# GD32E230C8T6.net
KiCad netlist of a schematic drawn in Altium Designer
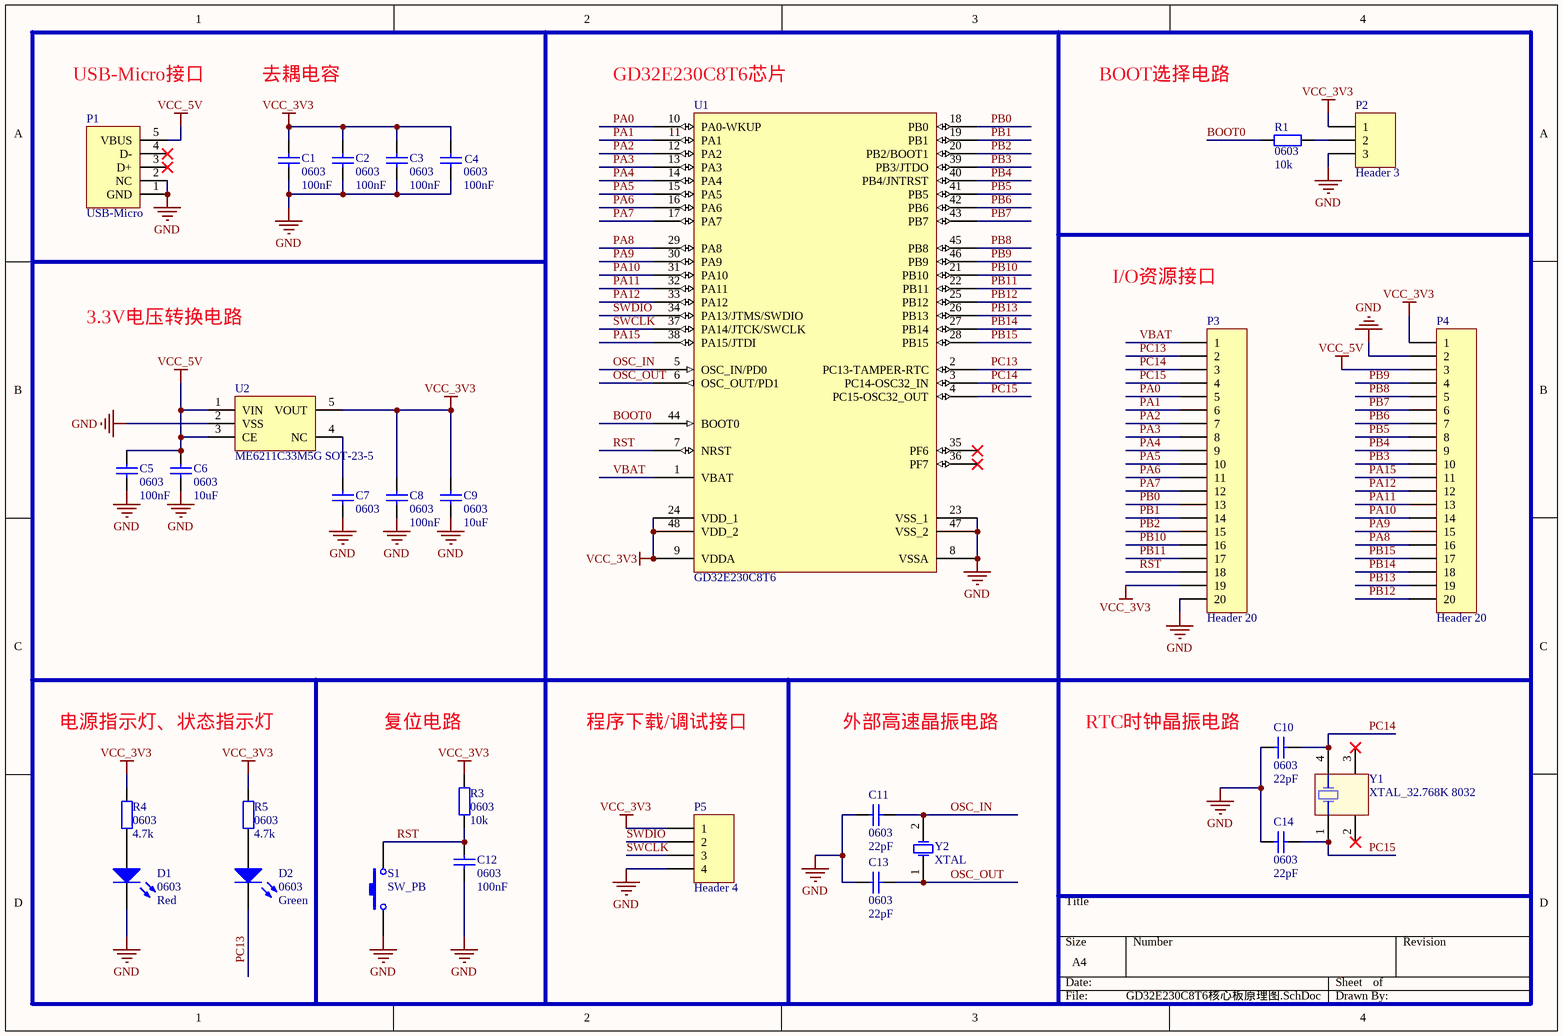
[diagram p0: GD32E230C8T6核心板原理图.SchDoc]

(export (version "E")
  (design (tool "Eeschema 10.0.6"))
  (components
    (comp (ref "C1")
      (value "100nF")
      (footprint "0603")
      (description "Capacitor 0603")
      (fields (field (name "Comment") "Cap 0603"))
      (libsource (lib "Schlib1") (part "Cap 0603"))
    )
    (comp (ref "C2")
      (value "100nF")
      (footprint "0603")
      (description "Capacitor 0603")
      (fields (field (name "Comment") "Cap 0603"))
      (libsource (lib "Schlib1") (part "Cap 0603"))
    )
    (comp (ref "C3")
      (value "100nF")
      (footprint "0603")
      (description "Capacitor 0603")
      (fields (field (name "Comment") "Cap 0603"))
      (libsource (lib "Schlib1") (part "Cap 0603"))
    )
    (comp (ref "C4")
      (value "100nF")
      (footprint "0603")
      (description "Capacitor 0603")
      (fields (field (name "Comment") "Cap 0603"))
      (libsource (lib "Schlib1") (part "Cap 0603"))
    )
    (comp (ref "C5")
      (value "100nF")
      (footprint "0603")
      (description "Capacitor 0603")
      (fields (field (name "Comment") "Cap 0603"))
      (libsource (lib "Schlib1") (part "Cap 0603"))
    )
    (comp (ref "C6")
      (value "10uF")
      (footprint "0603")
      (description "Capacitor 0603")
      (fields (field (name "Comment") "Cap 0603"))
      (libsource (lib "Schlib1") (part "Cap 0603"))
    )
    (comp (ref "C7")
      (value "Cap 0603")
      (footprint "0603")
      (description "Capacitor 0603")
      (libsource (lib "Schlib1") (part "Cap 0603"))
    )
    (comp (ref "C8")
      (value "100nF")
      (footprint "0603")
      (description "Capacitor 0603")
      (fields (field (name "Comment") "Cap 0603"))
      (libsource (lib "Schlib1") (part "Cap 0603"))
    )
    (comp (ref "C9")
      (value "10uF")
      (footprint "0603")
      (description "Capacitor 0603")
      (fields (field (name "Comment") "Cap 0603"))
      (libsource (lib "Schlib1") (part "Cap 0603"))
    )
    (comp (ref "C10")
      (value "22pF")
      (footprint "0603")
      (description "Capacitor 0603")
      (fields (field (name "Comment") "Cap 0603"))
      (libsource (lib "Schlib1") (part "Cap 0603"))
    )
    (comp (ref "C11")
      (value "22pF")
      (footprint "0603")
      (description "Capacitor 0603")
      (fields (field (name "Comment") "Cap 0603"))
      (libsource (lib "Schlib1") (part "Cap 0603"))
    )
    (comp (ref "C12")
      (value "100nF")
      (footprint "0603")
      (description "Capacitor 0603")
      (fields (field (name "Comment") "Cap 0603"))
      (libsource (lib "Schlib1") (part "Cap 0603"))
    )
    (comp (ref "C13")
      (value "22pF")
      (footprint "0603")
      (description "Capacitor 0603")
      (fields (field (name "Comment") "Cap 0603"))
      (libsource (lib "Schlib1") (part "Cap 0603"))
    )
    (comp (ref "C14")
      (value "22pF")
      (footprint "0603")
      (description "Capacitor 0603")
      (fields (field (name "Comment") "Cap 0603"))
      (libsource (lib "Schlib1") (part "Cap 0603"))
    )
    (comp (ref "D1")
      (value "Red")
      (footprint "0603")
      (description "LED 0603")
      (libsource (lib "Schlib1") (part "LED 0603"))
    )
    (comp (ref "D2")
      (value "Green")
      (footprint "0603")
      (description "LED 0603")
      (libsource (lib "Schlib1") (part "LED 0603"))
    )
    (comp (ref "P1")
      (value "USB-Micro")
      (footprint "USB Micro")
      (libsource (lib "Schlib1") (part "USB-Micro"))
    )
    (comp (ref "P2")
      (value "Header 3")
      (footprint "HDR1X3")
      (description "Header, 3-Pin")
      (fields (field (name "PUBLISHER") "Altium Limited"))
      (libsource (lib "Miscellaneous Connectors") (part "Header 3"))
    )
    (comp (ref "P3")
      (value "Header 20")
      (footprint "HDR1X20")
      (description "Header, 20-Pin")
      (fields (field (name "PUBLISHER") "Altium Limited"))
      (libsource (lib "Miscellaneous Connectors") (part "Header 20"))
    )
    (comp (ref "P4")
      (value "Header 20")
      (footprint "HDR1X20")
      (description "Header, 20-Pin")
      (fields (field (name "PUBLISHER") "Altium Limited"))
      (libsource (lib "Miscellaneous Connectors") (part "Header 20"))
    )
    (comp (ref "P5")
      (value "Header 4")
      (footprint "HDR1X4")
      (description "Header, 4-Pin")
      (fields (field (name "PUBLISHER") "Altium Limited"))
      (libsource (lib "Miscellaneous Connectors") (part "Header 4"))
    )
    (comp (ref "R1")
      (value "10k")
      (footprint "0603")
      (description "Resistor 0603")
      (fields (field (name "Comment") "Res 0603"))
      (libsource (lib "Schlib1") (part "Res 0603"))
    )
    (comp (ref "R3")
      (value "10k")
      (footprint "0603")
      (description "Resistor 0603")
      (fields (field (name "Comment") "Res 0603"))
      (libsource (lib "") (part "Res 0603_1"))
    )
    (comp (ref "R4")
      (value "4.7k")
      (footprint "0603")
      (description "Resistor 0603")
      (fields (field (name "Comment") "Res 0603"))
      (libsource (lib "") (part "Res 0603_2"))
    )
    (comp (ref "R5")
      (value "4.7k")
      (footprint "0603")
      (description "Resistor 0603")
      (fields (field (name "Comment") "Res 0603"))
      (libsource (lib "") (part "Res 0603_2"))
    )
    (comp (ref "S1") (value "SW_PB") (footprint "SW-2Pin") (libsource (lib "Schlib1") (part "SW_PB")))
    (comp (ref "U1")
      (value "GD32E230C8T6")
      (footprint "TQFP48_M")
      (description "STM32F030C8T6 LQFP48")
      (libsource (lib "STM32F103C8T6核心板原理图") (part "STM32F030C8T6"))
    )
    (comp (ref "U2")
      (value "ME6211C33M5G SOT-23-5")
      (footprint "SOT-23-5")
      (libsource (lib "Schlib1") (part "ME6211C33M5G"))
    )
    (comp (ref "Y1")
      (value "XTAL_32.768K 8032")
      (footprint "XTAL_8032")
      (libsource (lib "Schlib1") (part "XTAL_32.768K 8032"))
    )
    (comp (ref "Y2")
      (value "XTAL")
      (footprint "XTAL_49S")
      (description "XTAL 8MHZ")
      (libsource (lib "Schlib1") (part "XTAL 8MHZ"))
    )
  )
  (nets
    (net (code "1") (name "/BOOT0") (class "Default")
      (node (ref "R1") (pin "1") (pinfunction "1_1") (pintype "passive"))
      (node (ref "U1") (pin "44") (pinfunction "BOOT0_44") (pintype "input"))
    )
    (net (code "2") (name "/OSC_IN") (class "Default")
      (node (ref "C11") (pin "1") (pinfunction "1_1") (pintype "passive"))
      (node (ref "U1") (pin "5") (pinfunction "OSC_IN/PD0_5") (pintype "input"))
      (node (ref "Y2") (pin "2") (pinfunction "OSC2_2") (pintype "passive"))
    )
    (net (code "3") (name "/OSC_OUT") (class "Default")
      (node (ref "C13") (pin "1") (pinfunction "1_1") (pintype "passive"))
      (node (ref "U1") (pin "6") (pinfunction "OSC_OUT/PD1_6") (pintype "output"))
      (node (ref "Y2") (pin "1") (pinfunction "OSC1_1") (pintype "passive"))
    )
    (net (code "4") (name "/PA0") (class "Default")
      (node (ref "P3") (pin "5") (pinfunction "5_5") (pintype "passive"))
      (node (ref "U1") (pin "10") (pinfunction "PA0-WKUP_10") (pintype "bidirectional"))
    )
    (net (code "5") (name "/PA1") (class "Default")
      (node (ref "P3") (pin "6") (pinfunction "6_6") (pintype "passive"))
      (node (ref "U1") (pin "11") (pinfunction "PA1_11") (pintype "bidirectional"))
    )
    (net (code "6") (name "/PA2") (class "Default")
      (node (ref "P3") (pin "7") (pinfunction "7_7") (pintype "passive"))
      (node (ref "U1") (pin "12") (pinfunction "PA2_12") (pintype "bidirectional"))
    )
    (net (code "7") (name "/PA3") (class "Default")
      (node (ref "P3") (pin "8") (pinfunction "8_8") (pintype "passive"))
      (node (ref "U1") (pin "13") (pinfunction "PA3_13") (pintype "bidirectional"))
    )
    (net (code "8") (name "/PA4") (class "Default")
      (node (ref "P3") (pin "9") (pinfunction "9_9") (pintype "passive"))
      (node (ref "U1") (pin "14") (pinfunction "PA4_14") (pintype "bidirectional"))
    )
    (net (code "9") (name "/PA5") (class "Default")
      (node (ref "P3") (pin "10") (pinfunction "10_10") (pintype "passive"))
      (node (ref "U1") (pin "15") (pinfunction "PA5_15") (pintype "bidirectional"))
    )
    (net (code "10") (name "/PA6") (class "Default")
      (node (ref "P3") (pin "11") (pinfunction "11_11") (pintype "passive"))
      (node (ref "U1") (pin "16") (pinfunction "PA6_16") (pintype "bidirectional"))
    )
    (net (code "11") (name "/PA7") (class "Default")
      (node (ref "P3") (pin "12") (pinfunction "12_12") (pintype "passive"))
      (node (ref "U1") (pin "17") (pinfunction "PA7_17") (pintype "bidirectional"))
    )
    (net (code "12") (name "/PA8") (class "Default")
      (node (ref "P4") (pin "16") (pinfunction "16_16") (pintype "passive"))
      (node (ref "U1") (pin "29") (pinfunction "PA8_29") (pintype "bidirectional"))
    )
    (net (code "13") (name "/PA9") (class "Default")
      (node (ref "P4") (pin "15") (pinfunction "15_15") (pintype "passive"))
      (node (ref "U1") (pin "30") (pinfunction "PA9_30") (pintype "bidirectional"))
    )
    (net (code "14") (name "/PA10") (class "Default")
      (node (ref "P4") (pin "14") (pinfunction "14_14") (pintype "passive"))
      (node (ref "U1") (pin "31") (pinfunction "PA10_31") (pintype "bidirectional"))
    )
    (net (code "15") (name "/PA11") (class "Default")
      (node (ref "P4") (pin "13") (pinfunction "13_13") (pintype "passive"))
      (node (ref "U1") (pin "32") (pinfunction "PA11_32") (pintype "bidirectional"))
    )
    (net (code "16") (name "/PA12") (class "Default")
      (node (ref "P4") (pin "12") (pinfunction "12_12") (pintype "passive"))
      (node (ref "U1") (pin "33") (pinfunction "PA12_33") (pintype "bidirectional"))
    )
    (net (code "17") (name "/PA15") (class "Default")
      (node (ref "P4") (pin "11") (pinfunction "11_11") (pintype "passive"))
      (node (ref "U1") (pin "38") (pinfunction "PA15/JTDI_38") (pintype "bidirectional"))
    )
    (net (code "18") (name "/PB0") (class "Default")
      (node (ref "P3") (pin "13") (pinfunction "13_13") (pintype "passive"))
      (node (ref "U1") (pin "18") (pinfunction "PB0_18") (pintype "bidirectional"))
    )
    (net (code "19") (name "/PB1") (class "Default")
      (node (ref "P3") (pin "14") (pinfunction "14_14") (pintype "passive"))
      (node (ref "U1") (pin "19") (pinfunction "PB1_19") (pintype "bidirectional"))
    )
    (net (code "20") (name "/PB2") (class "Default")
      (node (ref "P3") (pin "15") (pinfunction "15_15") (pintype "passive"))
      (node (ref "U1") (pin "20") (pinfunction "PB2/BOOT1_20") (pintype "bidirectional"))
    )
    (net (code "21") (name "/PB3") (class "Default")
      (node (ref "P4") (pin "10") (pinfunction "10_10") (pintype "passive"))
      (node (ref "U1") (pin "39") (pinfunction "PB3/JTDO_39") (pintype "bidirectional"))
    )
    (net (code "22") (name "/PB4") (class "Default")
      (node (ref "P4") (pin "9") (pinfunction "9_9") (pintype "passive"))
      (node (ref "U1") (pin "40") (pinfunction "PB4/JNTRST_40") (pintype "bidirectional"))
    )
    (net (code "23") (name "/PB5") (class "Default")
      (node (ref "P4") (pin "8") (pinfunction "8_8") (pintype "passive"))
      (node (ref "U1") (pin "41") (pinfunction "PB5_41") (pintype "bidirectional"))
    )
    (net (code "24") (name "/PB6") (class "Default")
      (node (ref "P4") (pin "7") (pinfunction "7_7") (pintype "passive"))
      (node (ref "U1") (pin "42") (pinfunction "PB6_42") (pintype "bidirectional"))
    )
    (net (code "25") (name "/PB7") (class "Default")
      (node (ref "P4") (pin "6") (pinfunction "6_6") (pintype "passive"))
      (node (ref "U1") (pin "43") (pinfunction "PB7_43") (pintype "bidirectional"))
    )
    (net (code "26") (name "/PB8") (class "Default")
      (node (ref "P4") (pin "5") (pinfunction "5_5") (pintype "passive"))
      (node (ref "U1") (pin "45") (pinfunction "PB8_45") (pintype "bidirectional"))
    )
    (net (code "27") (name "/PB9") (class "Default")
      (node (ref "P4") (pin "4") (pinfunction "4_4") (pintype "passive"))
      (node (ref "U1") (pin "46") (pinfunction "PB9_46") (pintype "bidirectional"))
    )
    (net (code "28") (name "/PB10") (class "Default")
      (node (ref "P3") (pin "16") (pinfunction "16_16") (pintype "passive"))
      (node (ref "U1") (pin "21") (pinfunction "PB10_21") (pintype "bidirectional"))
    )
    (net (code "29") (name "/PB11") (class "Default")
      (node (ref "P3") (pin "17") (pinfunction "17_17") (pintype "passive"))
      (node (ref "U1") (pin "22") (pinfunction "PB11_22") (pintype "bidirectional"))
    )
    (net (code "30") (name "/PB12") (class "Default")
      (node (ref "P4") (pin "20") (pinfunction "20_20") (pintype "passive"))
      (node (ref "U1") (pin "25") (pinfunction "PB12_25") (pintype "bidirectional"))
    )
    (net (code "31") (name "/PB13") (class "Default")
      (node (ref "P4") (pin "19") (pinfunction "19_19") (pintype "passive"))
      (node (ref "U1") (pin "26") (pinfunction "PB13_26") (pintype "bidirectional"))
    )
    (net (code "32") (name "/PB14") (class "Default")
      (node (ref "P4") (pin "18") (pinfunction "18_18") (pintype "passive"))
      (node (ref "U1") (pin "27") (pinfunction "PB14_27") (pintype "bidirectional"))
    )
    (net (code "33") (name "/PB15") (class "Default")
      (node (ref "P4") (pin "17") (pinfunction "17_17") (pintype "passive"))
      (node (ref "U1") (pin "28") (pinfunction "PB15_28") (pintype "bidirectional"))
    )
    (net (code "34") (name "/PC13") (class "Default")
      (node (ref "D2") (pin "2") (pinfunction "K_2") (pintype "passive"))
      (node (ref "P3") (pin "2") (pinfunction "2_2") (pintype "passive"))
      (node (ref "U1") (pin "2") (pinfunction "PC13-TAMPER-RTC_2") (pintype "bidirectional"))
    )
    (net (code "35") (name "/PC14") (class "Default")
      (node (ref "C10") (pin "1") (pinfunction "1_1") (pintype "passive"))
      (node (ref "P3") (pin "3") (pinfunction "3_3") (pintype "passive"))
      (node (ref "U1") (pin "3") (pinfunction "PC14-OSC32_IN_3") (pintype "bidirectional"))
      (node (ref "Y1") (pin "4") (pinfunction "OSC2_4") (pintype "passive"))
    )
    (net (code "36") (name "/PC15") (class "Default")
      (node (ref "C14") (pin "1") (pinfunction "1_1") (pintype "passive"))
      (node (ref "P3") (pin "4") (pinfunction "4_4") (pintype "passive"))
      (node (ref "U1") (pin "4") (pinfunction "PC15-OSC32_OUT_4") (pintype "bidirectional"))
      (node (ref "Y1") (pin "1") (pinfunction "OSC1_1") (pintype "passive"))
    )
    (net (code "37") (name "/RST") (class "Default")
      (node (ref "C12") (pin "2") (pinfunction "2_2") (pintype "passive"))
      (node (ref "P3") (pin "18") (pinfunction "18_18") (pintype "passive"))
      (node (ref "R3") (pin "1") (pinfunction "1_1") (pintype "passive"))
      (node (ref "S1") (pin "2") (pinfunction "2_2") (pintype "passive"))
      (node (ref "U1") (pin "7") (pinfunction "NRST_7") (pintype "bidirectional"))
    )
    (net (code "38") (name "/SWCLK") (class "Default")
      (node (ref "P5") (pin "3") (pinfunction "3_3") (pintype "passive"))
      (node (ref "U1") (pin "37") (pinfunction "PA14/JTCK/SWCLK_37") (pintype "bidirectional"))
    )
    (net (code "39") (name "/SWDIO") (class "Default")
      (node (ref "P5") (pin "2") (pinfunction "2_2") (pintype "passive"))
      (node (ref "U1") (pin "34") (pinfunction "PA13/JTMS/SWDIO_34") (pintype "bidirectional"))
    )
    (net (code "40") (name "/VBAT") (class "Default")
      (node (ref "P3") (pin "1") (pinfunction "1_1") (pintype "passive"))
      (node (ref "U1") (pin "1") (pinfunction "VBAT_1") (pintype "power_in"))
    )
    (net (code "41") (name "GND") (class "Default")
      (node (ref "C1") (pin "1") (pinfunction "1_1") (pintype "passive"))
      (node (ref "C10") (pin "2") (pinfunction "2_2") (pintype "passive"))
      (node (ref "C11") (pin "2") (pinfunction "2_2") (pintype "passive"))
      (node (ref "C12") (pin "1") (pinfunction "1_1") (pintype "passive"))
      (node (ref "C13") (pin "2") (pinfunction "2_2") (pintype "passive"))
      (node (ref "C14") (pin "2") (pinfunction "2_2") (pintype "passive"))
      (node (ref "C2") (pin "1") (pinfunction "1_1") (pintype "passive"))
      (node (ref "C3") (pin "1") (pinfunction "1_1") (pintype "passive"))
      (node (ref "C4") (pin "1") (pinfunction "1_1") (pintype "passive"))
      (node (ref "C5") (pin "1") (pinfunction "1_1") (pintype "passive"))
      (node (ref "C6") (pin "1") (pinfunction "1_1") (pintype "passive"))
      (node (ref "C7") (pin "1") (pinfunction "1_1") (pintype "passive"))
      (node (ref "C8") (pin "1") (pinfunction "1_1") (pintype "passive"))
      (node (ref "C9") (pin "1") (pinfunction "1_1") (pintype "passive"))
      (node (ref "D1") (pin "2") (pinfunction "K_2") (pintype "passive"))
      (node (ref "P1") (pin "1") (pinfunction "GND_1") (pintype "power_in"))
      (node (ref "P1") (pin "2") (pinfunction "NC_2") (pintype "power_in"))
      (node (ref "P2") (pin "3") (pinfunction "3_3") (pintype "passive"))
      (node (ref "P3") (pin "20") (pinfunction "20_20") (pintype "passive"))
      (node (ref "P4") (pin "2") (pinfunction "2_2") (pintype "passive"))
      (node (ref "P5") (pin "4") (pinfunction "4_4") (pintype "passive"))
      (node (ref "S1") (pin "1") (pinfunction "1_1") (pintype "passive"))
      (node (ref "U1") (pin "23") (pinfunction "VSS_1_23") (pintype "power_in"))
      (node (ref "U1") (pin "47") (pinfunction "VSS_2_47") (pintype "power_in"))
      (node (ref "U1") (pin "8") (pinfunction "VSSA_8") (pintype "power_in"))
      (node (ref "U2") (pin "2") (pinfunction "VSS_2") (pintype "power_in"))
    )
    (net (code "42") (name "Net-(D1-A)") (class "Default")
      (node (ref "D1") (pin "1") (pinfunction "A_1") (pintype "passive"))
      (node (ref "R4") (pin "2") (pinfunction "2_2") (pintype "passive"))
    )
    (net (code "43") (name "Net-(D2-A)") (class "Default")
      (node (ref "D2") (pin "1") (pinfunction "A_1") (pintype "passive"))
      (node (ref "R5") (pin "2") (pinfunction "2_2") (pintype "passive"))
    )
    (net (code "44") (name "Net-(P2-Pad2)") (class "Default")
      (node (ref "P2") (pin "2") (pinfunction "2_2") (pintype "passive"))
      (node (ref "R1") (pin "2") (pinfunction "2_2") (pintype "passive"))
    )
    (net (code "45") (name "Net-(U2-NC)") (class "Default")
      (node (ref "C7") (pin "2") (pinfunction "2_2") (pintype "passive"))
      (node (ref "U2") (pin "4") (pinfunction "NC_4") (pintype "power_in"))
    )
    (net (code "46") (name "VCC_3V3") (class "Default")
      (node (ref "C1") (pin "2") (pinfunction "2_2") (pintype "passive"))
      (node (ref "C2") (pin "2") (pinfunction "2_2") (pintype "passive"))
      (node (ref "C3") (pin "2") (pinfunction "2_2") (pintype "passive"))
      (node (ref "C4") (pin "2") (pinfunction "2_2") (pintype "passive"))
      (node (ref "C8") (pin "2") (pinfunction "2_2") (pintype "passive"))
      (node (ref "C9") (pin "2") (pinfunction "2_2") (pintype "passive"))
      (node (ref "P2") (pin "1") (pinfunction "1_1") (pintype "passive"))
      (node (ref "P3") (pin "19") (pinfunction "19_19") (pintype "passive"))
      (node (ref "P4") (pin "1") (pinfunction "1_1") (pintype "passive"))
      (node (ref "P5") (pin "1") (pinfunction "1_1") (pintype "passive"))
      (node (ref "R3") (pin "2") (pinfunction "2_2") (pintype "passive"))
      (node (ref "R4") (pin "1") (pinfunction "1_1") (pintype "passive"))
      (node (ref "R5") (pin "1") (pinfunction "1_1") (pintype "passive"))
      (node (ref "U1") (pin "24") (pinfunction "VDD_1_24") (pintype "power_in"))
      (node (ref "U1") (pin "48") (pinfunction "VDD_2_48") (pintype "power_in"))
      (node (ref "U1") (pin "9") (pinfunction "VDDA_9") (pintype "power_in"))
      (node (ref "U2") (pin "5") (pinfunction "VOUT_5") (pintype "power_in"))
    )
    (net (code "47") (name "VCC_5V") (class "Default")
      (node (ref "C5") (pin "2") (pinfunction "2_2") (pintype "passive"))
      (node (ref "C6") (pin "2") (pinfunction "2_2") (pintype "passive"))
      (node (ref "P1") (pin "5") (pinfunction "VBUS_5") (pintype "power_in"))
      (node (ref "P4") (pin "3") (pinfunction "3_3") (pintype "passive"))
      (node (ref "U2") (pin "1") (pinfunction "VIN_1") (pintype "power_in"))
      (node (ref "U2") (pin "3") (pinfunction "CE_3") (pintype "power_in"))
    )
    (net (code "48") (name "unconnected-(P1-D+-Pad3)") (class "Default")
      (node (ref "P1") (pin "3") (pinfunction "D+_3") (pintype "power_in+no_connect"))
    )
    (net (code "49") (name "unconnected-(P1-D--Pad4)") (class "Default")
      (node (ref "P1") (pin "4") (pinfunction "D-_4") (pintype "power_in+no_connect"))
    )
    (net (code "50") (name "unconnected-(U1-PF6-Pad35)") (class "Default")
      (node (ref "U1") (pin "35") (pinfunction "PF6_35") (pintype "bidirectional+no_connect"))
    )
    (net (code "51") (name "unconnected-(U1-PF7-Pad36)") (class "Default")
      (node (ref "U1") (pin "36") (pinfunction "PF7_36") (pintype "bidirectional+no_connect"))
    )
    (net (code "52") (name "unconnected-(Y1-NC-Pad2)") (class "Default")
      (node (ref "Y1") (pin "2") (pinfunction "NC_2") (pintype "power_in+no_connect"))
    )
    (net (code "53") (name "unconnected-(Y1-NC-Pad3)") (class "Default")
      (node (ref "Y1") (pin "3") (pinfunction "NC_3") (pintype "power_in+no_connect"))
    )
  )
)
